# Optocoupler_circuit.net
KiCad netlist of a schematic drawn in Altium Designer
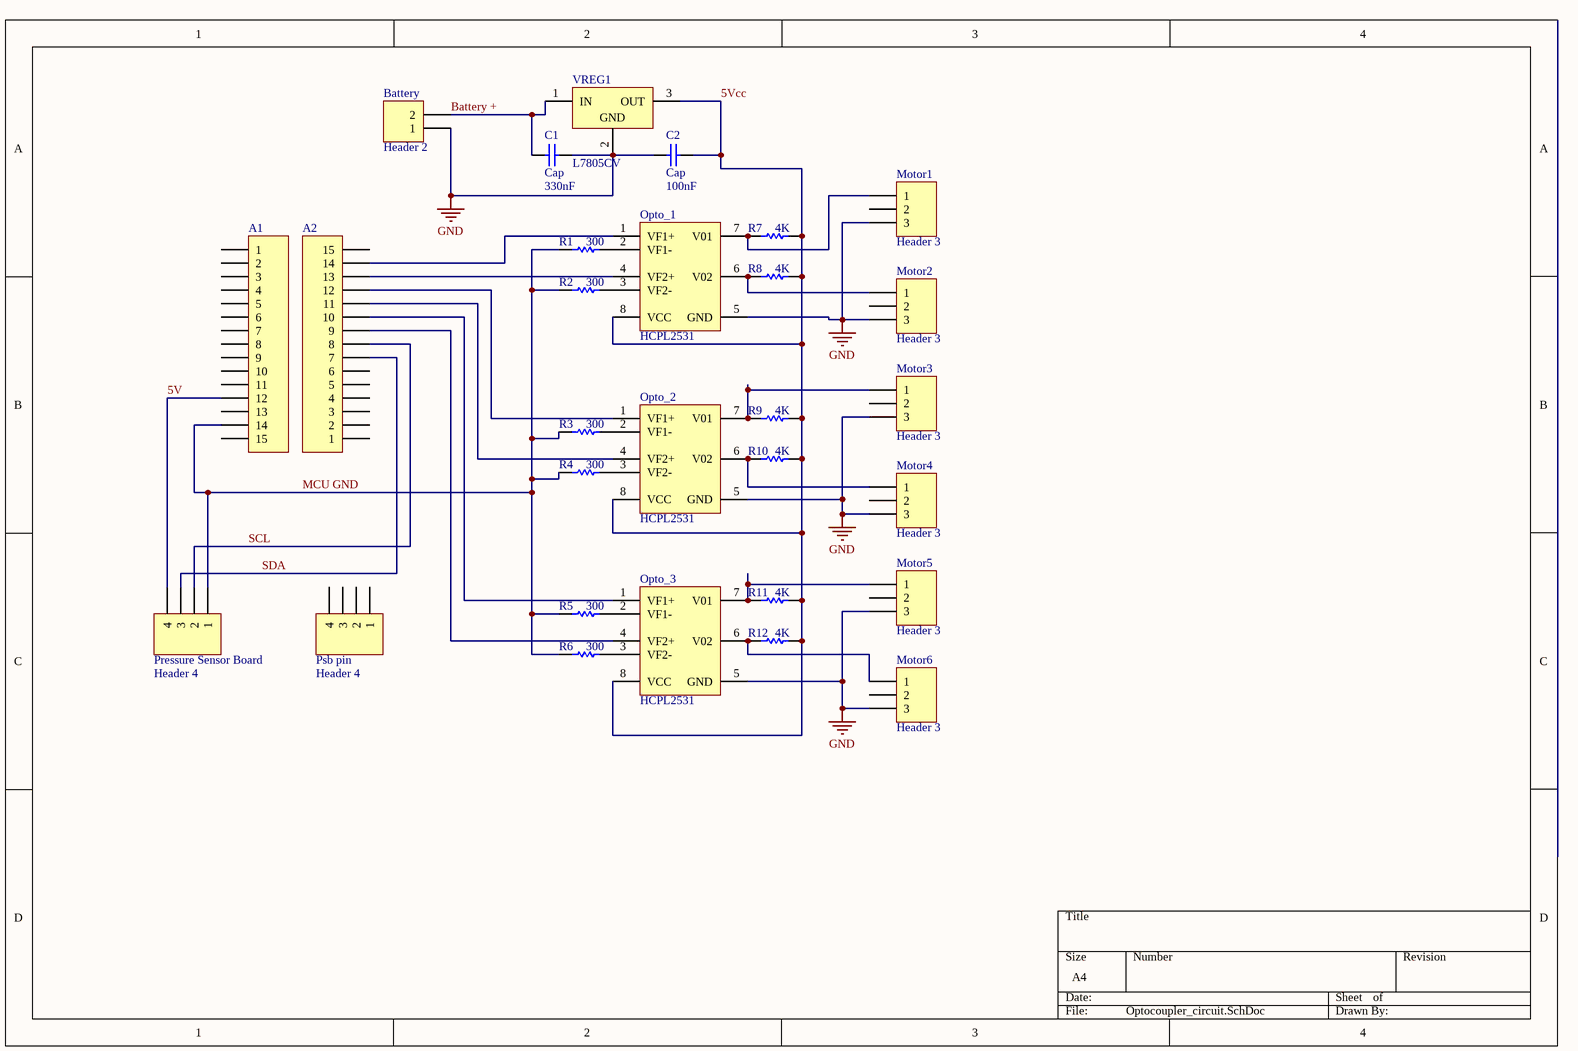
[diagram p0: Optocoupler_circuit.SchDoc]

(export (version "E")
  (design (tool "Eeschema 10.0.6"))
  (components
    (comp (ref "A1")
      (value "Header 15")
      (footprint "HDR1X15")
      (description "Header, 15-Pin")
      (fields (field (name "PUBLISHER") "Altium Limited"))
      (libsource (lib "") (part "Header 15_1"))
    )
    (comp (ref "A2")
      (value "Header 15")
      (footprint "HDR1X15")
      (description "Header, 15-Pin")
      (fields (field (name "PUBLISHER") "Altium Limited"))
      (libsource (lib "Miscellaneous Connectors") (part "Header 15"))
    )
    (comp (ref "Battery")
      (value "Header 2")
      (footprint "HDR1X2")
      (description "Header, 2-Pin")
      (fields (field (name "PUBLISHER") "Altium Limited"))
      (libsource (lib "Miscellaneous Connectors") (part "Header 2"))
    )
    (comp (ref "C1")
      (value "Cap")
      (footprint "HDR1X2")
      (description "Capacitor")
      (fields (field (name "ALTIUM_VALUE") "330nF") (field (name "PUBLISHER") "Altium Limited"))
      (libsource (lib "Miscellaneous Devices") (part "Cap"))
    )
    (comp (ref "C2")
      (value "Cap")
      (footprint "HDR1X2")
      (description "Capacitor")
      (fields (field (name "ALTIUM_VALUE") "100nF") (field (name "PUBLISHER") "Altium Limited"))
      (libsource (lib "Miscellaneous Devices") (part "Cap"))
    )
    (comp (ref "Motor1")
      (value "Header 3")
      (footprint "HDR1X3")
      (description "Header, 3-Pin")
      (fields (field (name "PUBLISHER") "Altium Limited"))
      (libsource (lib "Miscellaneous Connectors") (part "Header 3"))
    )
    (comp (ref "Motor2")
      (value "Header 3")
      (footprint "HDR1X3")
      (description "Header, 3-Pin")
      (fields (field (name "PUBLISHER") "Altium Limited"))
      (libsource (lib "Miscellaneous Connectors") (part "Header 3"))
    )
    (comp (ref "Motor3")
      (value "Header 3")
      (footprint "HDR1X3")
      (description "Header, 3-Pin")
      (fields (field (name "PUBLISHER") "Altium Limited"))
      (libsource (lib "Miscellaneous Connectors") (part "Header 3"))
    )
    (comp (ref "Motor4")
      (value "Header 3")
      (footprint "HDR1X3")
      (description "Header, 3-Pin")
      (fields (field (name "PUBLISHER") "Altium Limited"))
      (libsource (lib "Miscellaneous Connectors") (part "Header 3"))
    )
    (comp (ref "Motor5")
      (value "Header 3")
      (footprint "HDR1X3")
      (description "Header, 3-Pin")
      (fields (field (name "PUBLISHER") "Altium Limited"))
      (libsource (lib "Miscellaneous Connectors") (part "Header 3"))
    )
    (comp (ref "Motor6")
      (value "Header 3")
      (footprint "HDR1X3")
      (description "Header, 3-Pin")
      (fields (field (name "PUBLISHER") "Altium Limited"))
      (libsource (lib "Miscellaneous Connectors") (part "Header 3"))
    )
    (comp (ref "Opto_1")
      (value "HCPL2531")
      (footprint "FAIR-MDIP-8")
      (fields (field (name "MANUFACTURER") "FairchildSemiconductor"))
      (libsource (lib "Altium Content Vault") (part "FAIR-HCPL2531-DIP-8"))
    )
    (comp (ref "Opto_2")
      (value "HCPL2531")
      (footprint "FAIR-MDIP-8")
      (fields (field (name "MANUFACTURER") "FairchildSemiconductor"))
      (libsource (lib "Altium Content Vault") (part "FAIR-HCPL2531-DIP-8"))
    )
    (comp (ref "Opto_3")
      (value "HCPL2531")
      (footprint "FAIR-MDIP-8")
      (fields (field (name "MANUFACTURER") "FairchildSemiconductor"))
      (libsource (lib "Altium Content Vault") (part "FAIR-HCPL2531-DIP-8"))
    )
    (comp (ref "Pressure Sensor Board")
      (value "Header 4")
      (footprint "HDR1X4")
      (description "Header, 4-Pin")
      (fields (field (name "PUBLISHER") "Altium Limited"))
      (libsource (lib "Miscellaneous Connectors") (part "Header 4"))
    )
    (comp (ref "Psb pin")
      (value "Header 4")
      (footprint "HDR1X4")
      (description "Header, 4-Pin")
      (fields (field (name "PUBLISHER") "Altium Limited"))
      (libsource (lib "Miscellaneous Connectors") (part "Header 4"))
    )
    (comp (ref "R1")
      (value "300")
      (footprint "AXIAL-0.3")
      (description "Resistor")
      (fields (field (name "PUBLISHER") "Altium Limited"))
      (libsource (lib "Miscellaneous Devices") (part "Res1"))
    )
    (comp (ref "R2")
      (value "300")
      (footprint "AXIAL-0.3")
      (description "Resistor")
      (fields (field (name "PUBLISHER") "Altium Limited"))
      (libsource (lib "Miscellaneous Devices") (part "Res1"))
    )
    (comp (ref "R3")
      (value "300")
      (footprint "AXIAL-0.3")
      (description "Resistor")
      (fields (field (name "PUBLISHER") "Altium Limited"))
      (libsource (lib "Miscellaneous Devices") (part "Res1"))
    )
    (comp (ref "R4")
      (value "300")
      (footprint "AXIAL-0.3")
      (description "Resistor")
      (fields (field (name "PUBLISHER") "Altium Limited"))
      (libsource (lib "Miscellaneous Devices") (part "Res1"))
    )
    (comp (ref "R5")
      (value "300")
      (footprint "AXIAL-0.3")
      (description "Resistor")
      (fields (field (name "PUBLISHER") "Altium Limited"))
      (libsource (lib "Miscellaneous Devices") (part "Res1"))
    )
    (comp (ref "R6")
      (value "300")
      (footprint "AXIAL-0.3")
      (description "Resistor")
      (fields (field (name "PUBLISHER") "Altium Limited"))
      (libsource (lib "Miscellaneous Devices") (part "Res1"))
    )
    (comp (ref "R7")
      (value "4K")
      (footprint "AXIAL-0.3")
      (description "Resistor")
      (fields (field (name "Comment") "300") (field (name "PUBLISHER") "Altium Limited"))
      (libsource (lib "Miscellaneous Devices") (part "Res1"))
    )
    (comp (ref "R8")
      (value "4K")
      (footprint "AXIAL-0.3")
      (description "Resistor")
      (fields (field (name "Comment") "300") (field (name "PUBLISHER") "Altium Limited"))
      (libsource (lib "Miscellaneous Devices") (part "Res1"))
    )
    (comp (ref "R9")
      (value "4K")
      (footprint "AXIAL-0.3")
      (description "Resistor")
      (fields (field (name "Comment") "300") (field (name "PUBLISHER") "Altium Limited"))
      (libsource (lib "Miscellaneous Devices") (part "Res1"))
    )
    (comp (ref "R10")
      (value "4K")
      (footprint "AXIAL-0.3")
      (description "Resistor")
      (fields (field (name "Comment") "300") (field (name "PUBLISHER") "Altium Limited"))
      (libsource (lib "Miscellaneous Devices") (part "Res1"))
    )
    (comp (ref "R11")
      (value "4K")
      (footprint "AXIAL-0.3")
      (description "Resistor")
      (fields (field (name "Comment") "300") (field (name "PUBLISHER") "Altium Limited"))
      (libsource (lib "Miscellaneous Devices") (part "Res1"))
    )
    (comp (ref "R12")
      (value "4K")
      (footprint "AXIAL-0.3")
      (description "Resistor")
      (fields (field (name "Comment") "300") (field (name "PUBLISHER") "Altium Limited"))
      (libsource (lib "Miscellaneous Devices") (part "Res1"))
    )
    (comp (ref "VREG1")
      (value "L7805CV")
      (footprint "TO220")
      (description "Positive Voltage Regulator, 5V, 3-Pin TO-220")
      (libsource (lib "Altium Content Vault") (part "PM-REG-L4940-SIL3"))
    )
  )
  (nets
    (net (code "1") (name "/5V") (class "Default")
      (node (ref "A1") (pin "12") (pinfunction "12_12") (pintype "passive"))
      (node (ref "Pressure Sensor Board") (pin "4") (pinfunction "4_4") (pintype "passive"))
    )
    (net (code "2") (name "/5Vcc") (class "Default")
      (node (ref "C2") (pin "2") (pinfunction "2_2") (pintype "passive"))
      (node (ref "Opto_1") (pin "8") (pinfunction "VCC_8") (pintype "power_in"))
      (node (ref "Opto_2") (pin "8") (pinfunction "VCC_8") (pintype "power_in"))
      (node (ref "Opto_3") (pin "8") (pinfunction "VCC_8") (pintype "power_in"))
      (node (ref "R10") (pin "2") (pinfunction "2_2") (pintype "passive"))
      (node (ref "R11") (pin "2") (pinfunction "2_2") (pintype "passive"))
      (node (ref "R12") (pin "2") (pinfunction "2_2") (pintype "passive"))
      (node (ref "R7") (pin "2") (pinfunction "2_2") (pintype "passive"))
      (node (ref "R8") (pin "2") (pinfunction "2_2") (pintype "passive"))
      (node (ref "R9") (pin "2") (pinfunction "2_2") (pintype "passive"))
      (node (ref "VREG1") (pin "3") (pinfunction "OUT_3") (pintype "power_in"))
    )
    (net (code "3") (name "/Battery +") (class "Default")
      (node (ref "Battery") (pin "2") (pinfunction "2_2") (pintype "passive"))
      (node (ref "C1") (pin "1") (pinfunction "1_1") (pintype "passive"))
      (node (ref "VREG1") (pin "1") (pinfunction "IN_1") (pintype "power_in"))
    )
    (net (code "4") (name "/MCU GND") (class "Default")
      (node (ref "A1") (pin "14") (pinfunction "14_14") (pintype "passive"))
      (node (ref "Pressure Sensor Board") (pin "1") (pinfunction "1_1") (pintype "passive"))
      (node (ref "R1") (pin "1") (pinfunction "1_1") (pintype "passive"))
      (node (ref "R2") (pin "1") (pinfunction "1_1") (pintype "passive"))
      (node (ref "R3") (pin "1") (pinfunction "1_1") (pintype "passive"))
      (node (ref "R4") (pin "1") (pinfunction "1_1") (pintype "passive"))
      (node (ref "R5") (pin "1") (pinfunction "1_1") (pintype "passive"))
      (node (ref "R6") (pin "1") (pinfunction "1_1") (pintype "passive"))
    )
    (net (code "5") (name "/SCL") (class "Default")
      (node (ref "A2") (pin "8") (pinfunction "8_8") (pintype "passive"))
      (node (ref "Pressure Sensor Board") (pin "2") (pinfunction "2_2") (pintype "passive"))
    )
    (net (code "6") (name "/SDA") (class "Default")
      (node (ref "A2") (pin "7") (pinfunction "7_7") (pintype "passive"))
      (node (ref "Pressure Sensor Board") (pin "3") (pinfunction "3_3") (pintype "passive"))
    )
    (net (code "7") (name "GND") (class "Default")
      (node (ref "Battery") (pin "1") (pinfunction "1_1") (pintype "passive"))
      (node (ref "C1") (pin "2") (pinfunction "2_2") (pintype "passive"))
      (node (ref "C2") (pin "1") (pinfunction "1_1") (pintype "passive"))
      (node (ref "Motor1") (pin "3") (pinfunction "3_3") (pintype "passive"))
      (node (ref "Motor2") (pin "3") (pinfunction "3_3") (pintype "passive"))
      (node (ref "Motor3") (pin "3") (pinfunction "3_3") (pintype "passive"))
      (node (ref "Motor4") (pin "3") (pinfunction "3_3") (pintype "passive"))
      (node (ref "Motor5") (pin "3") (pinfunction "3_3") (pintype "passive"))
      (node (ref "Motor6") (pin "3") (pinfunction "3_3") (pintype "passive"))
      (node (ref "Opto_1") (pin "5") (pinfunction "GND_5") (pintype "power_in"))
      (node (ref "Opto_2") (pin "5") (pinfunction "GND_5") (pintype "power_in"))
      (node (ref "Opto_3") (pin "5") (pinfunction "GND_5") (pintype "power_in"))
      (node (ref "VREG1") (pin "2") (pinfunction "GND_2") (pintype "power_in"))
    )
    (net (code "8") (name "Net-(Opto_1-V01)") (class "Default")
      (node (ref "Motor1") (pin "1") (pinfunction "1_1") (pintype "passive"))
      (node (ref "Opto_1") (pin "7") (pinfunction "V01_7") (pintype "passive"))
      (node (ref "R7") (pin "1") (pinfunction "1_1") (pintype "passive"))
    )
    (net (code "9") (name "Net-(Opto_1-V02)") (class "Default")
      (node (ref "Motor2") (pin "1") (pinfunction "1_1") (pintype "passive"))
      (node (ref "Opto_1") (pin "6") (pinfunction "V02_6") (pintype "passive"))
      (node (ref "R8") (pin "1") (pinfunction "1_1") (pintype "passive"))
    )
    (net (code "10") (name "Net-(Opto_1-VF1+)") (class "Default")
      (node (ref "A2") (pin "14") (pinfunction "14_14") (pintype "passive"))
      (node (ref "Opto_1") (pin "1") (pinfunction "VF1+_1") (pintype "passive"))
    )
    (net (code "11") (name "Net-(Opto_1-VF1-)") (class "Default")
      (node (ref "Opto_1") (pin "2") (pinfunction "VF1-_2") (pintype "passive"))
      (node (ref "R1") (pin "2") (pinfunction "2_2") (pintype "passive"))
    )
    (net (code "12") (name "Net-(Opto_1-VF2+)") (class "Default")
      (node (ref "A2") (pin "13") (pinfunction "13_13") (pintype "passive"))
      (node (ref "Opto_1") (pin "4") (pinfunction "VF2+_4") (pintype "passive"))
    )
    (net (code "13") (name "Net-(Opto_1-VF2-)") (class "Default")
      (node (ref "Opto_1") (pin "3") (pinfunction "VF2-_3") (pintype "passive"))
      (node (ref "R2") (pin "2") (pinfunction "2_2") (pintype "passive"))
    )
    (net (code "14") (name "Net-(Opto_2-V01)") (class "Default")
      (node (ref "Motor3") (pin "1") (pinfunction "1_1") (pintype "passive"))
      (node (ref "Opto_2") (pin "7") (pinfunction "V01_7") (pintype "passive"))
      (node (ref "R9") (pin "1") (pinfunction "1_1") (pintype "passive"))
    )
    (net (code "15") (name "Net-(Opto_2-V02)") (class "Default")
      (node (ref "Motor4") (pin "1") (pinfunction "1_1") (pintype "passive"))
      (node (ref "Opto_2") (pin "6") (pinfunction "V02_6") (pintype "passive"))
      (node (ref "R10") (pin "1") (pinfunction "1_1") (pintype "passive"))
    )
    (net (code "16") (name "Net-(Opto_2-VF1+)") (class "Default")
      (node (ref "A2") (pin "12") (pinfunction "12_12") (pintype "passive"))
      (node (ref "Opto_2") (pin "1") (pinfunction "VF1+_1") (pintype "passive"))
    )
    (net (code "17") (name "Net-(Opto_2-VF1-)") (class "Default")
      (node (ref "Opto_2") (pin "2") (pinfunction "VF1-_2") (pintype "passive"))
      (node (ref "R3") (pin "2") (pinfunction "2_2") (pintype "passive"))
    )
    (net (code "18") (name "Net-(Opto_2-VF2+)") (class "Default")
      (node (ref "A2") (pin "11") (pinfunction "11_11") (pintype "passive"))
      (node (ref "Opto_2") (pin "4") (pinfunction "VF2+_4") (pintype "passive"))
    )
    (net (code "19") (name "Net-(Opto_2-VF2-)") (class "Default")
      (node (ref "Opto_2") (pin "3") (pinfunction "VF2-_3") (pintype "passive"))
      (node (ref "R4") (pin "2") (pinfunction "2_2") (pintype "passive"))
    )
    (net (code "20") (name "Net-(Opto_3-V01)") (class "Default")
      (node (ref "Motor5") (pin "1") (pinfunction "1_1") (pintype "passive"))
      (node (ref "Opto_3") (pin "7") (pinfunction "V01_7") (pintype "passive"))
      (node (ref "R11") (pin "1") (pinfunction "1_1") (pintype "passive"))
    )
    (net (code "21") (name "Net-(Opto_3-V02)") (class "Default")
      (node (ref "Motor6") (pin "1") (pinfunction "1_1") (pintype "passive"))
      (node (ref "Opto_3") (pin "6") (pinfunction "V02_6") (pintype "passive"))
      (node (ref "R12") (pin "1") (pinfunction "1_1") (pintype "passive"))
    )
    (net (code "22") (name "Net-(Opto_3-VF1+)") (class "Default")
      (node (ref "A2") (pin "10") (pinfunction "10_10") (pintype "passive"))
      (node (ref "Opto_3") (pin "1") (pinfunction "VF1+_1") (pintype "passive"))
    )
    (net (code "23") (name "Net-(Opto_3-VF1-)") (class "Default")
      (node (ref "Opto_3") (pin "2") (pinfunction "VF1-_2") (pintype "passive"))
      (node (ref "R5") (pin "2") (pinfunction "2_2") (pintype "passive"))
    )
    (net (code "24") (name "Net-(Opto_3-VF2+)") (class "Default")
      (node (ref "A2") (pin "9") (pinfunction "9_9") (pintype "passive"))
      (node (ref "Opto_3") (pin "4") (pinfunction "VF2+_4") (pintype "passive"))
    )
    (net (code "25") (name "Net-(Opto_3-VF2-)") (class "Default")
      (node (ref "Opto_3") (pin "3") (pinfunction "VF2-_3") (pintype "passive"))
      (node (ref "R6") (pin "2") (pinfunction "2_2") (pintype "passive"))
    )
    (net (code "26") (name "unconnected-(A1-Pad1)") (class "Default")
      (node (ref "A1") (pin "1") (pinfunction "1_1") (pintype "passive"))
    )
    (net (code "27") (name "unconnected-(A1-Pad2)") (class "Default")
      (node (ref "A1") (pin "2") (pinfunction "2_2") (pintype "passive"))
    )
    (net (code "28") (name "unconnected-(A1-Pad3)") (class "Default")
      (node (ref "A1") (pin "3") (pinfunction "3_3") (pintype "passive"))
    )
    (net (code "29") (name "unconnected-(A1-Pad4)") (class "Default")
      (node (ref "A1") (pin "4") (pinfunction "4_4") (pintype "passive"))
    )
    (net (code "30") (name "unconnected-(A1-Pad5)") (class "Default")
      (node (ref "A1") (pin "5") (pinfunction "5_5") (pintype "passive"))
    )
    (net (code "31") (name "unconnected-(A1-Pad6)") (class "Default")
      (node (ref "A1") (pin "6") (pinfunction "6_6") (pintype "passive"))
    )
    (net (code "32") (name "unconnected-(A1-Pad7)") (class "Default")
      (node (ref "A1") (pin "7") (pinfunction "7_7") (pintype "passive"))
    )
    (net (code "33") (name "unconnected-(A1-Pad8)") (class "Default")
      (node (ref "A1") (pin "8") (pinfunction "8_8") (pintype "passive"))
    )
    (net (code "34") (name "unconnected-(A1-Pad9)") (class "Default")
      (node (ref "A1") (pin "9") (pinfunction "9_9") (pintype "passive"))
    )
    (net (code "35") (name "unconnected-(A1-Pad10)") (class "Default")
      (node (ref "A1") (pin "10") (pinfunction "10_10") (pintype "passive"))
    )
    (net (code "36") (name "unconnected-(A1-Pad11)") (class "Default")
      (node (ref "A1") (pin "11") (pinfunction "11_11") (pintype "passive"))
    )
    (net (code "37") (name "unconnected-(A1-Pad13)") (class "Default")
      (node (ref "A1") (pin "13") (pinfunction "13_13") (pintype "passive"))
    )
    (net (code "38") (name "unconnected-(A1-Pad15)") (class "Default")
      (node (ref "A1") (pin "15") (pinfunction "15_15") (pintype "passive"))
    )
    (net (code "39") (name "unconnected-(A2-Pad1)") (class "Default")
      (node (ref "A2") (pin "1") (pinfunction "1_1") (pintype "passive"))
    )
    (net (code "40") (name "unconnected-(A2-Pad2)") (class "Default")
      (node (ref "A2") (pin "2") (pinfunction "2_2") (pintype "passive"))
    )
    (net (code "41") (name "unconnected-(A2-Pad3)") (class "Default")
      (node (ref "A2") (pin "3") (pinfunction "3_3") (pintype "passive"))
    )
    (net (code "42") (name "unconnected-(A2-Pad4)") (class "Default")
      (node (ref "A2") (pin "4") (pinfunction "4_4") (pintype "passive"))
    )
    (net (code "43") (name "unconnected-(A2-Pad5)") (class "Default")
      (node (ref "A2") (pin "5") (pinfunction "5_5") (pintype "passive"))
    )
    (net (code "44") (name "unconnected-(A2-Pad6)") (class "Default")
      (node (ref "A2") (pin "6") (pinfunction "6_6") (pintype "passive"))
    )
    (net (code "45") (name "unconnected-(A2-Pad15)") (class "Default")
      (node (ref "A2") (pin "15") (pinfunction "15_15") (pintype "passive"))
    )
    (net (code "46") (name "unconnected-(Motor1-Pad2)") (class "Default")
      (node (ref "Motor1") (pin "2") (pinfunction "2_2") (pintype "passive"))
    )
    (net (code "47") (name "unconnected-(Motor2-Pad2)") (class "Default")
      (node (ref "Motor2") (pin "2") (pinfunction "2_2") (pintype "passive"))
    )
    (net (code "48") (name "unconnected-(Motor3-Pad2)") (class "Default")
      (node (ref "Motor3") (pin "2") (pinfunction "2_2") (pintype "passive"))
    )
    (net (code "49") (name "unconnected-(Motor4-Pad2)") (class "Default")
      (node (ref "Motor4") (pin "2") (pinfunction "2_2") (pintype "passive"))
    )
    (net (code "50") (name "unconnected-(Motor5-Pad2)") (class "Default")
      (node (ref "Motor5") (pin "2") (pinfunction "2_2") (pintype "passive"))
    )
    (net (code "51") (name "unconnected-(Motor6-Pad2)") (class "Default")
      (node (ref "Motor6") (pin "2") (pinfunction "2_2") (pintype "passive"))
    )
    (net (code "52") (name "unconnected-(Psb pin-Pad1)") (class "Default")
      (node (ref "Psb pin") (pin "1") (pinfunction "1_1") (pintype "passive"))
    )
    (net (code "53") (name "unconnected-(Psb pin-Pad2)") (class "Default")
      (node (ref "Psb pin") (pin "2") (pinfunction "2_2") (pintype "passive"))
    )
    (net (code "54") (name "unconnected-(Psb pin-Pad3)") (class "Default")
      (node (ref "Psb pin") (pin "3") (pinfunction "3_3") (pintype "passive"))
    )
    (net (code "55") (name "unconnected-(Psb pin-Pad4)") (class "Default")
      (node (ref "Psb pin") (pin "4") (pinfunction "4_4") (pintype "passive"))
    )
  )
)
